# Main.net
KiCad netlist of a schematic drawn in Altium Designer
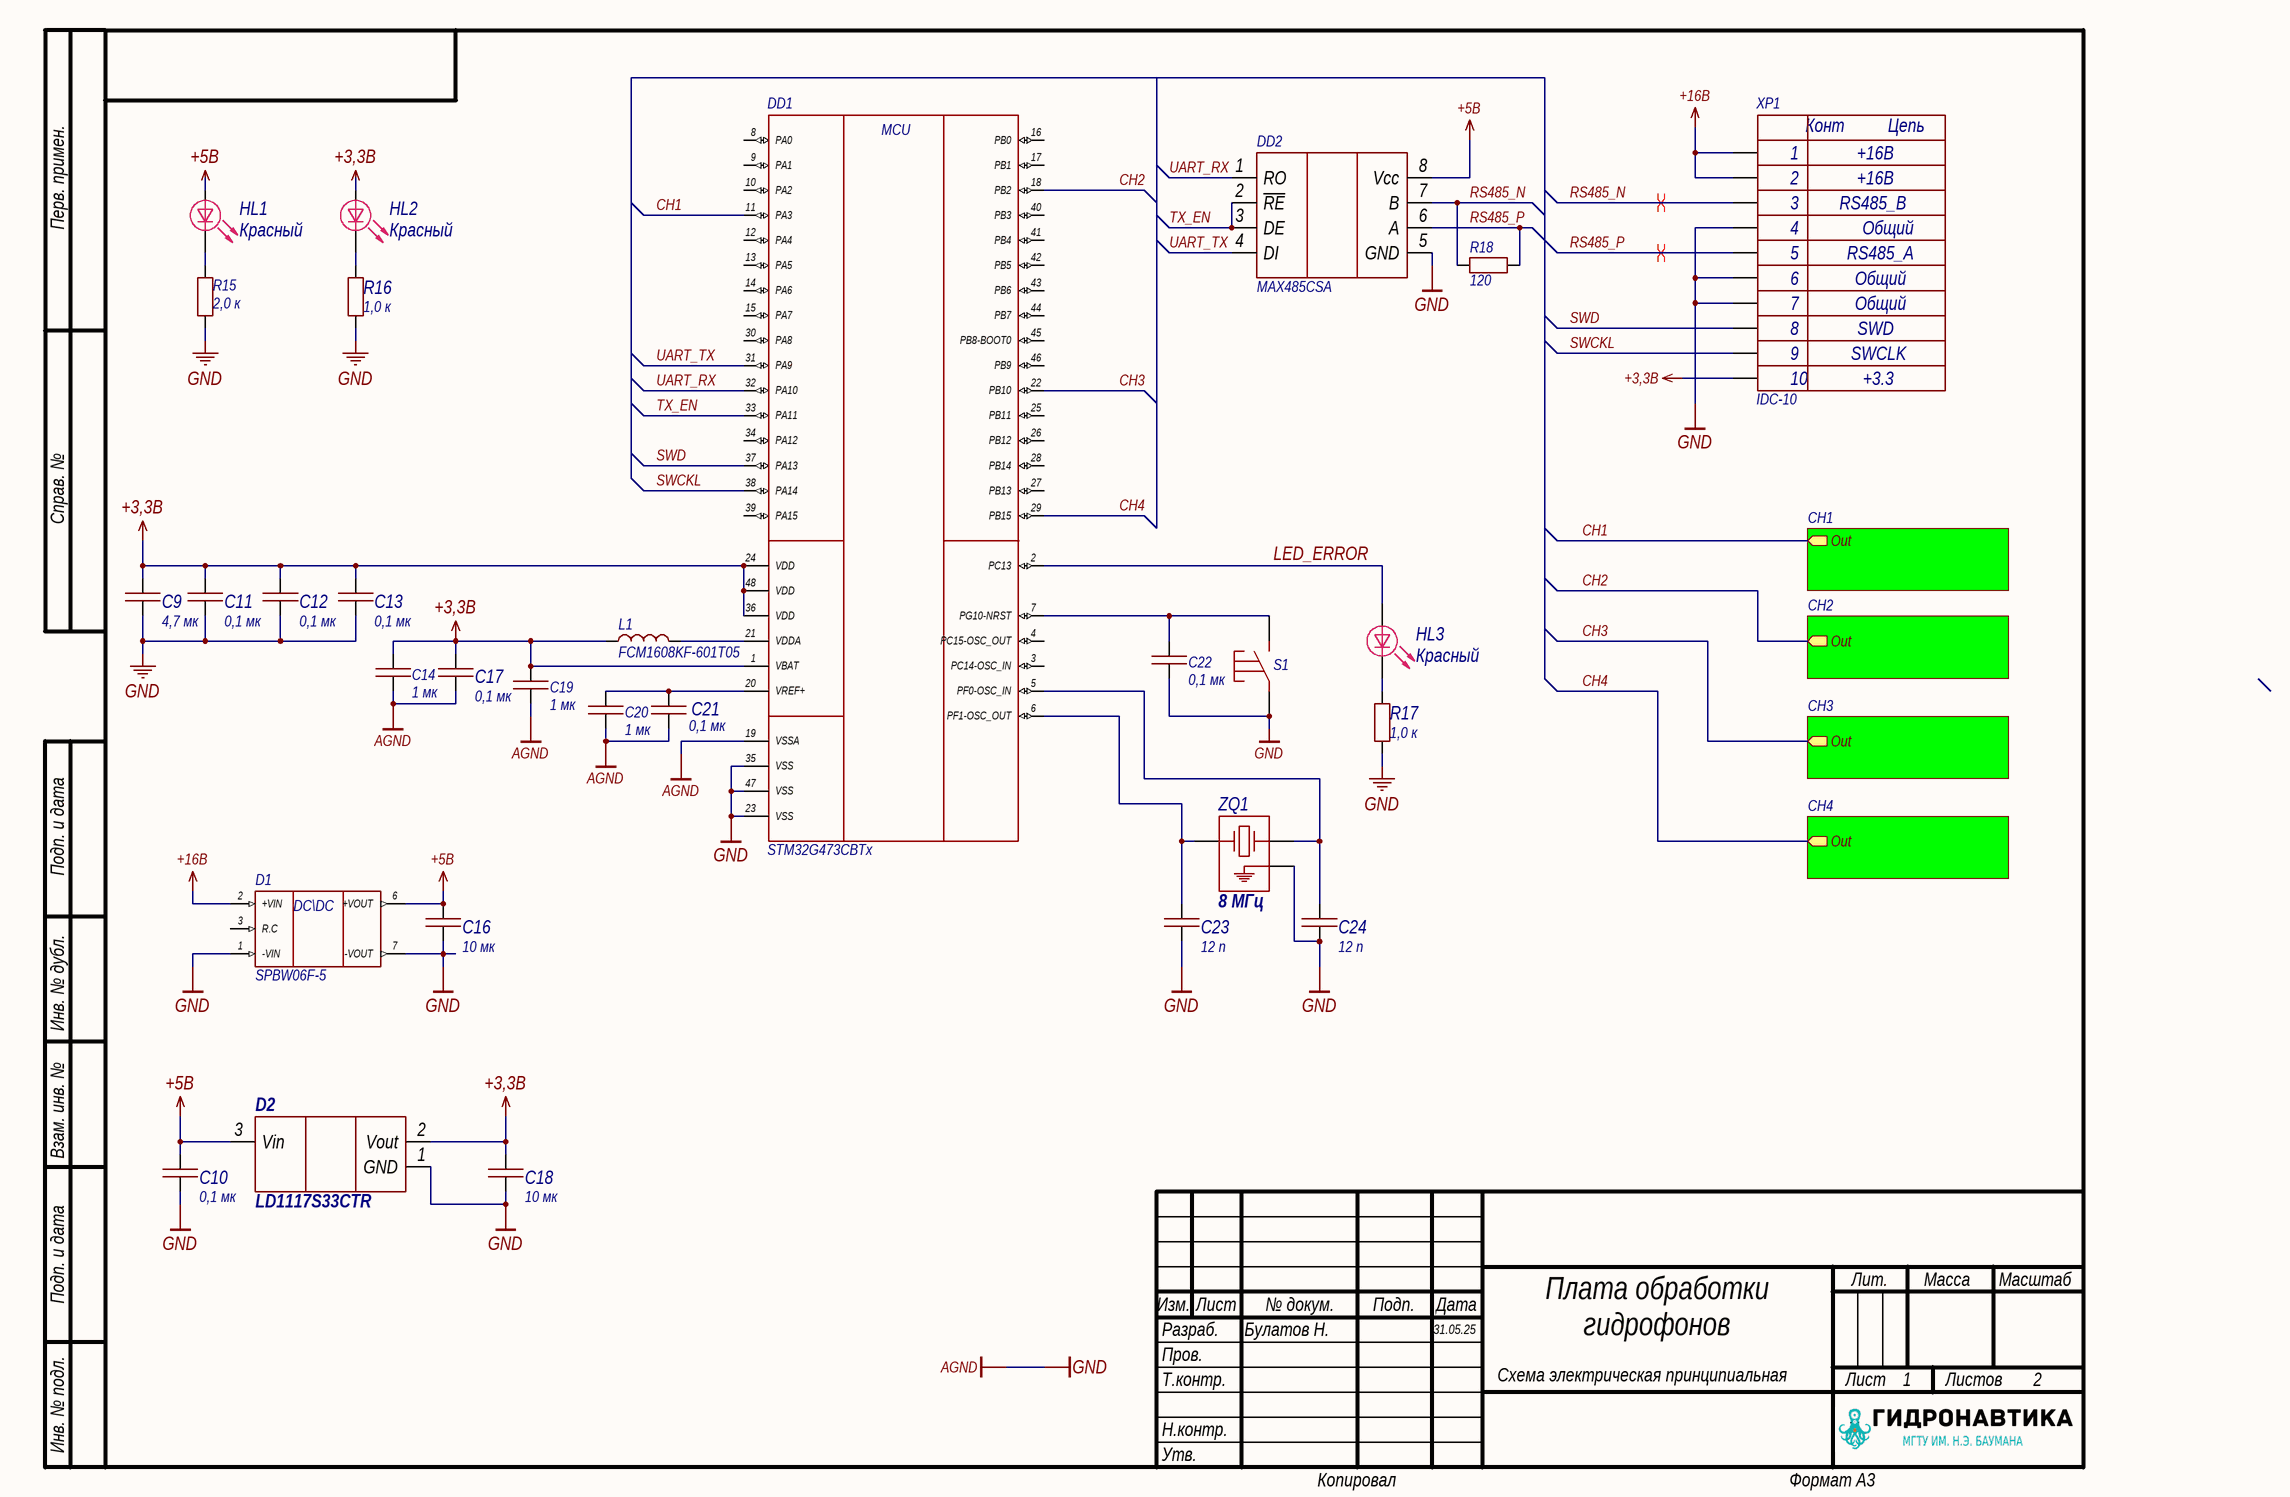
[diagram p0: Main.SchDoc]

(export (version "E")
  (design (tool "Eeschema 10.0.6"))
  (components
    (comp (ref "C9")
      (value "4,7 мк")
      (footprint "1206C")
      (description "Конденсатор")
      (fields (field (name "PART NUMBER") "Capacitor_4,7u_10_50V_X7R_1206C") (field (name "TOLERANCE") "0,1"))
      (libsource (lib "Hydrolib") (part "Capacitor"))
    )
    (comp (ref "C10")
      (value "0,1 мк")
      (footprint "0603C")
      (description "Конденсатор")
      (fields (field (name "PART NUMBER") "Capacitor_0,1u_10_50V_X7R_0603C") (field (name "TOLERANCE") "0,1"))
      (libsource (lib "Hydrolib") (part "Capacitor"))
    )
    (comp (ref "C11")
      (value "0,1 мк")
      (footprint "0603C")
      (description "Конденсатор")
      (fields (field (name "PART NUMBER") "Capacitor_0,1u_10_50V_X7R_0603C") (field (name "TOLERANCE") "0,1"))
      (libsource (lib "Hydrolib") (part "Capacitor"))
    )
    (comp (ref "C12")
      (value "0,1 мк")
      (footprint "0603C")
      (description "Конденсатор")
      (fields (field (name "PART NUMBER") "Capacitor_0,1u_10_50V_X7R_0603C") (field (name "TOLERANCE") "0,1"))
      (libsource (lib "Hydrolib") (part "Capacitor"))
    )
    (comp (ref "C13")
      (value "0,1 мк")
      (footprint "0603C")
      (description "Конденсатор")
      (fields (field (name "PART NUMBER") "Capacitor_0,1u_10_50V_X7R_0603C") (field (name "TOLERANCE") "0,1"))
      (libsource (lib "Hydrolib") (part "Capacitor"))
    )
    (comp (ref "C14")
      (value "1 мк")
      (footprint "0603C")
      (description "Конденсатор 0603C ёмкостью 1 мк 10%, 50 В, X7R")
      (fields (field (name "PART NUMBER") "Capacitor_1u_10_50V_X7R_0603C") (field (name "TOLERANCE") "10%"))
      (libsource (lib "Hydrolib") (part "Capacitor"))
    )
    (comp (ref "C16")
      (value "10 мк")
      (footprint "1210C")
      (description "Конденсатор")
      (fields (field (name "PART NUMBER") "Capacitor_10u_10_35V_X7R_1210C") (field (name "TOLERANCE") "0,1"))
      (libsource (lib "Hydrolib") (part "Capacitor"))
    )
    (comp (ref "C17")
      (value "0,1 мк")
      (footprint "0603C")
      (description "Конденсатор")
      (fields (field (name "PART NUMBER") "Capacitor_0,1u_10_50V_X7R_0603C") (field (name "TOLERANCE") "0,1"))
      (libsource (lib "Hydrolib") (part "Capacitor"))
    )
    (comp (ref "C18")
      (value "10 мк")
      (footprint "1210C")
      (description "Конденсатор")
      (fields (field (name "PART NUMBER") "Capacitor_10u_10_35V_X7R_1210C") (field (name "TOLERANCE") "0,1"))
      (libsource (lib "Hydrolib") (part "Capacitor"))
    )
    (comp (ref "C19")
      (value "1 мк")
      (footprint "0603C")
      (description "Конденсатор 0603C ёмкостью 1 мк 10%, 50 В, X7R")
      (fields (field (name "PART NUMBER") "Capacitor_1u_10_50V_X7R_0603C") (field (name "TOLERANCE") "10%"))
      (libsource (lib "Hydrolib") (part "Capacitor"))
    )
    (comp (ref "C20")
      (value "1 мк")
      (footprint "0603C")
      (description "Конденсатор 0603C ёмкостью 1 мк 10%, 50 В, X7R")
      (fields (field (name "PART NUMBER") "Capacitor_1u_10_50V_X7R_0603C") (field (name "TOLERANCE") "10%"))
      (libsource (lib "Hydrolib") (part "Capacitor"))
    )
    (comp (ref "C21")
      (value "0,1 мк")
      (footprint "0603C")
      (description "Конденсатор")
      (fields (field (name "PART NUMBER") "Capacitor_0,1u_10_50V_X7R_0603C") (field (name "TOLERANCE") "0,1"))
      (libsource (lib "Hydrolib") (part "Capacitor"))
    )
    (comp (ref "C22")
      (value "0,1 мк")
      (footprint "0603C")
      (description "Конденсатор 0603C ёмкостью 0,1 мк 10%, 50 В, X7R")
      (fields (field (name "PART NUMBER") "Capacitor_0,1u_10_50V_X7R_0603C") (field (name "TOLERANCE") "10%"))
      (libsource (lib "Hydrolib") (part "Capacitor"))
    )
    (comp (ref "C23")
      (value "12 п")
      (footprint "0603C")
      (description "Конденсатор 12п")
      (fields (field (name "PART NUMBER") "Capacitor"))
      (libsource (lib "Hydrolib") (part "Capacitor"))
    )
    (comp (ref "C24")
      (value "12 п")
      (footprint "0603C")
      (description "Конденсатор 12п")
      (fields (field (name "PART NUMBER") "Capacitor"))
      (libsource (lib "Hydrolib") (part "Capacitor"))
    )
    (comp (ref "D1")
      (value "SPBW06F-5")
      (footprint "CONV_SPBW06F-12")
      (description "Isolated Module DC DC Converter 1 Output 12V - - - 500mA 9V - 36V Input")
      (fields (field (name "MF") "MEAN WELL") (field (name "MP") "SPBW06F-12"))
      (libsource (lib "SPBW06F-12") (part "SPBW06F-12"))
    )
    (comp (ref "D2")
      (value "LD1117S33CTR")
      (footprint "SOT223")
      (description "Линейный стабилизатор напряжения")
      (libsource (lib "Hydrolib") (part "LD1117S33CTR"))
    )
    (comp (ref "DD1")
      (value "STM32G473CBTx")
      (footprint "LQFP48-7x7mm")
      (fields
        (field (name "MANUFACTURER_PART_NUMBER") "stm32g4_lqfp48_t1")
        (field (name "COPYRIGHT") "Copyright (C) 2016 Accelerated Designs. All rights reserved")
      )
      (libsource (lib "ST Microelectronics STM32 G4") (part "STM32G473CBTx"))
    )
    (comp (ref "DD2")
      (value "MAX485CSA")
      (footprint "SOIC-8")
      (description "RS-485 приёмопередатчик")
      (libsource (lib "Hydrolib") (part "MAX485CSA"))
    )
    (comp (ref "HL1")
      (value "LED")
      (footprint "0805D")
      (description "Светодиод")
      (fields (field (name "COLOR") "Красный"))
      (libsource (lib "Hydrolib") (part "LED"))
    )
    (comp (ref "HL2")
      (value "LED")
      (footprint "0805D")
      (description "Светодиод")
      (fields (field (name "COLOR") "Красный"))
      (libsource (lib "Hydrolib") (part "LED"))
    )
    (comp (ref "HL3")
      (value "LED")
      (footprint "0805D")
      (description "Светодиод")
      (fields (field (name "COLOR") "Красный"))
      (libsource (lib "Hydrolib") (part "LED"))
    )
    (comp (ref "L1")
      (value "FCM1608KF-601T05")
      (footprint "0603L")
      (description "Катушка индуктивности")
      (fields (field (name "PART NUMBER") "Inductance"))
      (libsource (lib "Hydrolib") (part "Inductance"))
    )
    (comp (ref "R15")
      (value "2,0 к")
      (footprint "0603R")
      (description "Резистор номиналом 2,0 кОм 1%")
      (fields (field (name "PART NUMBER") "Resistor_2.0k_1_0603") (field (name "TOLERANCE") "1%"))
      (libsource (lib "Hydrolib") (part "Resistor"))
    )
    (comp (ref "R16")
      (value "1,0 к")
      (footprint "0603R")
      (description "Резистор номиналом 1,0 кОм и точностью 1%")
      (fields (field (name "PART NUMBER") "Resistor_1.0k_1_0603") (field (name "TOLERANCE") "1%"))
      (libsource (lib "Hydrolib") (part "Resistor"))
    )
    (comp (ref "R17")
      (value "1,0 к")
      (footprint "0603R")
      (description "Резистор номиналом 1,0 кОм и точностью 1%")
      (fields (field (name "PART NUMBER") "Resistor_1.0k_1_0603") (field (name "TOLERANCE") "1%"))
      (libsource (lib "Hydrolib") (part "Resistor"))
    )
    (comp (ref "R18")
      (value "120")
      (footprint "0603R")
      (description "Резистор номиналом 120 Ом 1%")
      (fields (field (name "PART NUMBER") "Resistor_120_1_0603") (field (name "TOLERANCE") "1%"))
      (libsource (lib "") (part "Resistor_1"))
    )
    (comp (ref "S1")
      (value "TSS-TD-19XA-XTR")
      (footprint "TSS-TD-19XA-XTR")
      (description "Тактовая кнопка")
      (fields (field (name "АВТОР") "glebmih"))
      (libsource (lib "Hydrolib") (part "Tact_button"))
    )
    (comp (ref "XP1")
      (value "IDC-10")
      (footprint "IDC-10")
      (description "10-пиновый разъём с ключём")
      (fields
        (field (name "VALUE1") "+16В")
        (field (name "VALUE2") "+16В")
        (field (name "VALUE3") "Общий")
        (field (name "VALUE4") "Общий")
        (field (name "VALUE5") "RS485_A")
        (field (name "VALUE6") "RS485_B")
        (field (name "VALUE7") "Общий")
        (field (name "VALUE8") "SWD")
        (field (name "VALUE9") "SWCLK")
        (field (name "VALUE10") "+3.3")
      )
      (libsource (lib "Hydrolib") (part "Conn_10pin"))
    )
    (comp (ref "ZQ1")
      (value "8 МГц")
      (footprint "QSMD3.2x2.5")
      (description "Кварцевый резонатор с входом земли")
      (fields (field (name "PART NUMBER") "XTAL_GND"))
      (libsource (lib "Hydrolib") (part "XTAL_GND"))
    )
  )
  (nets
    (net (code "1") (name "+3,3В") (class "Default")
      (node (ref "C11") (pin "2") (pinfunction "2_2") (pintype "passive"))
      (node (ref "C12") (pin "2") (pinfunction "2_2") (pintype "passive"))
      (node (ref "C13") (pin "2") (pinfunction "2_2") (pintype "passive"))
      (node (ref "C14") (pin "2") (pinfunction "2_2") (pintype "passive"))
      (node (ref "C17") (pin "2") (pinfunction "2_2") (pintype "passive"))
      (node (ref "C18") (pin "2") (pinfunction "2_2") (pintype "passive"))
      (node (ref "C19") (pin "2") (pinfunction "2_2") (pintype "passive"))
      (node (ref "C9") (pin "2") (pinfunction "2_2") (pintype "passive"))
      (node (ref "D2") (pin "2") (pinfunction "Vout_2") (pintype "passive"))
      (node (ref "DD1") (pin "1") (pinfunction "VBAT_1") (pintype "power_in"))
      (node (ref "DD1") (pin "24") (pinfunction "VDD_24") (pintype "power_in"))
      (node (ref "DD1") (pin "36") (pinfunction "VDD_36") (pintype "power_in"))
      (node (ref "DD1") (pin "48") (pinfunction "VDD_48") (pintype "power_in"))
      (node (ref "HL2") (pin "1") (pinfunction "1_1") (pintype "passive"))
      (node (ref "L1") (pin "1") (pinfunction "1_1") (pintype "passive"))
      (node (ref "XP1") (pin "10") (pinfunction "10_10") (pintype "passive"))
    )
    (net (code "2") (name "+5В") (class "Default")
      (node (ref "C10") (pin "2") (pinfunction "2_2") (pintype "passive"))
      (node (ref "C16") (pin "2") (pinfunction "2_2") (pintype "passive"))
      (node (ref "D1") (pin "6") (pinfunction "+VOUT_6") (pintype "output"))
      (node (ref "D2") (pin "3") (pinfunction "Vin_3") (pintype "passive"))
      (node (ref "DD2") (pin "8") (pinfunction "Vcc_8") (pintype "passive"))
      (node (ref "HL1") (pin "1") (pinfunction "1_1") (pintype "passive"))
    )
    (net (code "3") (name "+16В") (class "Default")
      (node (ref "D1") (pin "2") (pinfunction "+VIN_2") (pintype "input"))
      (node (ref "XP1") (pin "1") (pinfunction "1_1") (pintype "passive"))
      (node (ref "XP1") (pin "2") (pinfunction "2_2") (pintype "passive"))
    )
    (net (code "4") (name "/CH1") (class "Default")
      (node (ref "DD1") (pin "11") (pinfunction "PA3_11") (pintype "bidirectional"))
    )
    (net (code "5") (name "/CH2") (class "Default")
      (node (ref "DD1") (pin "18") (pinfunction "PB2_18") (pintype "bidirectional"))
    )
    (net (code "6") (name "/CH3") (class "Default")
      (node (ref "DD1") (pin "22") (pinfunction "PB10_22") (pintype "bidirectional"))
    )
    (net (code "7") (name "/CH4") (class "Default")
      (node (ref "DD1") (pin "29") (pinfunction "PB15_29") (pintype "bidirectional"))
    )
    (net (code "8") (name "/LED_ERROR") (class "Default")
      (node (ref "DD1") (pin "2") (pinfunction "PC13_2") (pintype "bidirectional"))
      (node (ref "HL3") (pin "1") (pinfunction "1_1") (pintype "passive"))
    )
    (net (code "9") (name "/RS485_N") (class "Default")
      (node (ref "DD2") (pin "7") (pinfunction "B_7") (pintype "passive"))
      (node (ref "R18") (pin "2") (pinfunction "2_2") (pintype "passive"))
      (node (ref "XP1") (pin "3") (pinfunction "3_3") (pintype "passive"))
    )
    (net (code "10") (name "/RS485_P") (class "Default")
      (node (ref "DD2") (pin "6") (pinfunction "A_6") (pintype "passive"))
      (node (ref "R18") (pin "1") (pinfunction "1_1") (pintype "passive"))
      (node (ref "XP1") (pin "5") (pinfunction "5_5") (pintype "passive"))
    )
    (net (code "11") (name "/SWCKL") (class "Default")
      (node (ref "DD1") (pin "38") (pinfunction "PA14_38") (pintype "bidirectional"))
      (node (ref "XP1") (pin "9") (pinfunction "9_9") (pintype "passive"))
    )
    (net (code "12") (name "/SWD") (class "Default")
      (node (ref "DD1") (pin "37") (pinfunction "PA13_37") (pintype "bidirectional"))
      (node (ref "XP1") (pin "8") (pinfunction "8_8") (pintype "passive"))
    )
    (net (code "13") (name "/TX_EN") (class "Default")
      (node (ref "DD1") (pin "33") (pinfunction "PA11_33") (pintype "bidirectional"))
      (node (ref "DD2") (pin "2") (pinfunction "RE_2") (pintype "passive"))
      (node (ref "DD2") (pin "3") (pinfunction "DE_3") (pintype "passive"))
    )
    (net (code "14") (name "/UART_RX") (class "Default")
      (node (ref "DD1") (pin "32") (pinfunction "PA10_32") (pintype "bidirectional"))
      (node (ref "DD2") (pin "1") (pinfunction "RO_1") (pintype "passive"))
    )
    (net (code "15") (name "/UART_TX") (class "Default")
      (node (ref "DD1") (pin "31") (pinfunction "PA9_31") (pintype "bidirectional"))
      (node (ref "DD2") (pin "4") (pinfunction "DI_4") (pintype "passive"))
    )
    (net (code "16") (name "AGND") (class "Default")
      (node (ref "C10") (pin "1") (pinfunction "1_1") (pintype "passive"))
      (node (ref "C11") (pin "1") (pinfunction "1_1") (pintype "passive"))
      (node (ref "C12") (pin "1") (pinfunction "1_1") (pintype "passive"))
      (node (ref "C13") (pin "1") (pinfunction "1_1") (pintype "passive"))
      (node (ref "C14") (pin "1") (pinfunction "1_1") (pintype "passive"))
      (node (ref "C16") (pin "1") (pinfunction "1_1") (pintype "passive"))
      (node (ref "C17") (pin "1") (pinfunction "1_1") (pintype "passive"))
      (node (ref "C18") (pin "1") (pinfunction "1_1") (pintype "passive"))
      (node (ref "C19") (pin "1") (pinfunction "1_1") (pintype "passive"))
      (node (ref "C20") (pin "1") (pinfunction "1_1") (pintype "passive"))
      (node (ref "C21") (pin "1") (pinfunction "1_1") (pintype "passive"))
      (node (ref "C22") (pin "1") (pinfunction "1_1") (pintype "passive"))
      (node (ref "C23") (pin "1") (pinfunction "1_1") (pintype "passive"))
      (node (ref "C24") (pin "1") (pinfunction "1_1") (pintype "passive"))
      (node (ref "C9") (pin "1") (pinfunction "1_1") (pintype "passive"))
      (node (ref "D1") (pin "1") (pinfunction "-VIN_1") (pintype "input"))
      (node (ref "D1") (pin "7") (pinfunction "-VOUT_7") (pintype "output"))
      (node (ref "D2") (pin "1") (pinfunction "GND_1") (pintype "passive"))
      (node (ref "DD1") (pin "19") (pinfunction "VSSA_19") (pintype "power_in"))
      (node (ref "DD1") (pin "23") (pinfunction "VSS_23") (pintype "power_in"))
      (node (ref "DD1") (pin "35") (pinfunction "VSS_35") (pintype "power_in"))
      (node (ref "DD1") (pin "47") (pinfunction "VSS_47") (pintype "power_in"))
      (node (ref "DD2") (pin "5") (pinfunction "GND_5") (pintype "passive"))
      (node (ref "R15") (pin "1") (pinfunction "1_1") (pintype "passive"))
      (node (ref "R16") (pin "1") (pinfunction "1_1") (pintype "passive"))
      (node (ref "R17") (pin "1") (pinfunction "1_1") (pintype "passive"))
      (node (ref "S1") (pin "1") (pinfunction "1_1") (pintype "passive"))
      (node (ref "XP1") (pin "4") (pinfunction "4_4") (pintype "passive"))
      (node (ref "XP1") (pin "6") (pinfunction "6_6") (pintype "passive"))
      (node (ref "XP1") (pin "7") (pinfunction "7_7") (pintype "passive"))
      (node (ref "ZQ1") (pin "3") (pinfunction "3_3") (pintype "passive"))
    )
    (net (code "17") (name "Net-(DD1-PF0-OSC_IN)") (class "Default")
      (node (ref "C24") (pin "2") (pinfunction "2_2") (pintype "passive"))
      (node (ref "DD1") (pin "5") (pinfunction "PF0-OSC_IN_5") (pintype "bidirectional"))
      (node (ref "ZQ1") (pin "2") (pinfunction "2_2") (pintype "passive"))
    )
    (net (code "18") (name "Net-(DD1-PF1-OSC_OUT)") (class "Default")
      (node (ref "C23") (pin "2") (pinfunction "2_2") (pintype "passive"))
      (node (ref "DD1") (pin "6") (pinfunction "PF1-OSC_OUT_6") (pintype "bidirectional"))
      (node (ref "ZQ1") (pin "1") (pinfunction "1_1") (pintype "passive"))
    )
    (net (code "19") (name "Net-(DD1-PG10-NRST)") (class "Default")
      (node (ref "C22") (pin "2") (pinfunction "2_2") (pintype "passive"))
      (node (ref "DD1") (pin "7") (pinfunction "PG10-NRST_7") (pintype "bidirectional"))
      (node (ref "S1") (pin "2") (pinfunction "2_2") (pintype "passive"))
    )
    (net (code "20") (name "Net-(DD1-VDDA)") (class "Default")
      (node (ref "DD1") (pin "21") (pinfunction "VDDA_21") (pintype "power_in"))
      (node (ref "L1") (pin "2") (pinfunction "2_2") (pintype "passive"))
    )
    (net (code "21") (name "Net-(DD1-VREF+)") (class "Default")
      (node (ref "C20") (pin "2") (pinfunction "2_2") (pintype "passive"))
      (node (ref "C21") (pin "2") (pinfunction "2_2") (pintype "passive"))
      (node (ref "DD1") (pin "20") (pinfunction "VREF+_20") (pintype "power_in"))
    )
    (net (code "22") (name "Net-(HL1-Pad2)") (class "Default")
      (node (ref "HL1") (pin "2") (pinfunction "2_2") (pintype "passive"))
      (node (ref "R15") (pin "2") (pinfunction "2_2") (pintype "passive"))
    )
    (net (code "23") (name "Net-(HL2-Pad2)") (class "Default")
      (node (ref "HL2") (pin "2") (pinfunction "2_2") (pintype "passive"))
      (node (ref "R16") (pin "2") (pinfunction "2_2") (pintype "passive"))
    )
    (net (code "24") (name "Net-(HL3-Pad2)") (class "Default")
      (node (ref "HL3") (pin "2") (pinfunction "2_2") (pintype "passive"))
      (node (ref "R17") (pin "2") (pinfunction "2_2") (pintype "passive"))
    )
    (net (code "25") (name "unconnected-(D1-R.C-Pad3)") (class "Default")
      (node (ref "D1") (pin "3") (pinfunction "R.C_3") (pintype "input"))
    )
    (net (code "26") (name "unconnected-(DD1-PA0-Pad8)") (class "Default")
      (node (ref "DD1") (pin "8") (pinfunction "PA0_8") (pintype "bidirectional"))
    )
    (net (code "27") (name "unconnected-(DD1-PA1-Pad9)") (class "Default")
      (node (ref "DD1") (pin "9") (pinfunction "PA1_9") (pintype "bidirectional"))
    )
    (net (code "28") (name "unconnected-(DD1-PA2-Pad10)") (class "Default")
      (node (ref "DD1") (pin "10") (pinfunction "PA2_10") (pintype "bidirectional"))
    )
    (net (code "29") (name "unconnected-(DD1-PA4-Pad12)") (class "Default")
      (node (ref "DD1") (pin "12") (pinfunction "PA4_12") (pintype "bidirectional"))
    )
    (net (code "30") (name "unconnected-(DD1-PA5-Pad13)") (class "Default")
      (node (ref "DD1") (pin "13") (pinfunction "PA5_13") (pintype "bidirectional"))
    )
    (net (code "31") (name "unconnected-(DD1-PA6-Pad14)") (class "Default")
      (node (ref "DD1") (pin "14") (pinfunction "PA6_14") (pintype "bidirectional"))
    )
    (net (code "32") (name "unconnected-(DD1-PA7-Pad15)") (class "Default")
      (node (ref "DD1") (pin "15") (pinfunction "PA7_15") (pintype "bidirectional"))
    )
    (net (code "33") (name "unconnected-(DD1-PA8-Pad30)") (class "Default")
      (node (ref "DD1") (pin "30") (pinfunction "PA8_30") (pintype "bidirectional"))
    )
    (net (code "34") (name "unconnected-(DD1-PA12-Pad34)") (class "Default")
      (node (ref "DD1") (pin "34") (pinfunction "PA12_34") (pintype "bidirectional"))
    )
    (net (code "35") (name "unconnected-(DD1-PA15-Pad39)") (class "Default")
      (node (ref "DD1") (pin "39") (pinfunction "PA15_39") (pintype "bidirectional"))
    )
    (net (code "36") (name "unconnected-(DD1-PB0-Pad16)") (class "Default")
      (node (ref "DD1") (pin "16") (pinfunction "PB0_16") (pintype "bidirectional"))
    )
    (net (code "37") (name "unconnected-(DD1-PB1-Pad17)") (class "Default")
      (node (ref "DD1") (pin "17") (pinfunction "PB1_17") (pintype "bidirectional"))
    )
    (net (code "38") (name "unconnected-(DD1-PB3-Pad40)") (class "Default")
      (node (ref "DD1") (pin "40") (pinfunction "PB3_40") (pintype "bidirectional"))
    )
    (net (code "39") (name "unconnected-(DD1-PB4-Pad41)") (class "Default")
      (node (ref "DD1") (pin "41") (pinfunction "PB4_41") (pintype "bidirectional"))
    )
    (net (code "40") (name "unconnected-(DD1-PB5-Pad42)") (class "Default")
      (node (ref "DD1") (pin "42") (pinfunction "PB5_42") (pintype "bidirectional"))
    )
    (net (code "41") (name "unconnected-(DD1-PB6-Pad43)") (class "Default")
      (node (ref "DD1") (pin "43") (pinfunction "PB6_43") (pintype "bidirectional"))
    )
    (net (code "42") (name "unconnected-(DD1-PB7-Pad44)") (class "Default")
      (node (ref "DD1") (pin "44") (pinfunction "PB7_44") (pintype "bidirectional"))
    )
    (net (code "43") (name "unconnected-(DD1-PB8-BOOT0-Pad45)") (class "Default")
      (node (ref "DD1") (pin "45") (pinfunction "PB8-BOOT0_45") (pintype "bidirectional"))
    )
    (net (code "44") (name "unconnected-(DD1-PB9-Pad46)") (class "Default")
      (node (ref "DD1") (pin "46") (pinfunction "PB9_46") (pintype "bidirectional"))
    )
    (net (code "45") (name "unconnected-(DD1-PB11-Pad25)") (class "Default")
      (node (ref "DD1") (pin "25") (pinfunction "PB11_25") (pintype "bidirectional"))
    )
    (net (code "46") (name "unconnected-(DD1-PB12-Pad26)") (class "Default")
      (node (ref "DD1") (pin "26") (pinfunction "PB12_26") (pintype "bidirectional"))
    )
    (net (code "47") (name "unconnected-(DD1-PB13-Pad27)") (class "Default")
      (node (ref "DD1") (pin "27") (pinfunction "PB13_27") (pintype "bidirectional"))
    )
    (net (code "48") (name "unconnected-(DD1-PB14-Pad28)") (class "Default")
      (node (ref "DD1") (pin "28") (pinfunction "PB14_28") (pintype "bidirectional"))
    )
    (net (code "49") (name "unconnected-(DD1-PC14-OSC_IN-Pad3)") (class "Default")
      (node (ref "DD1") (pin "3") (pinfunction "PC14-OSC_IN_3") (pintype "bidirectional"))
    )
    (net (code "50") (name "unconnected-(DD1-PC15-OSC_OUT-Pad4)") (class "Default")
      (node (ref "DD1") (pin "4") (pinfunction "PC15-OSC_OUT_4") (pintype "bidirectional"))
    )
  )
)
